# UC3843_Boost.net
KiCad netlist of a schematic drawn in Altium Designer
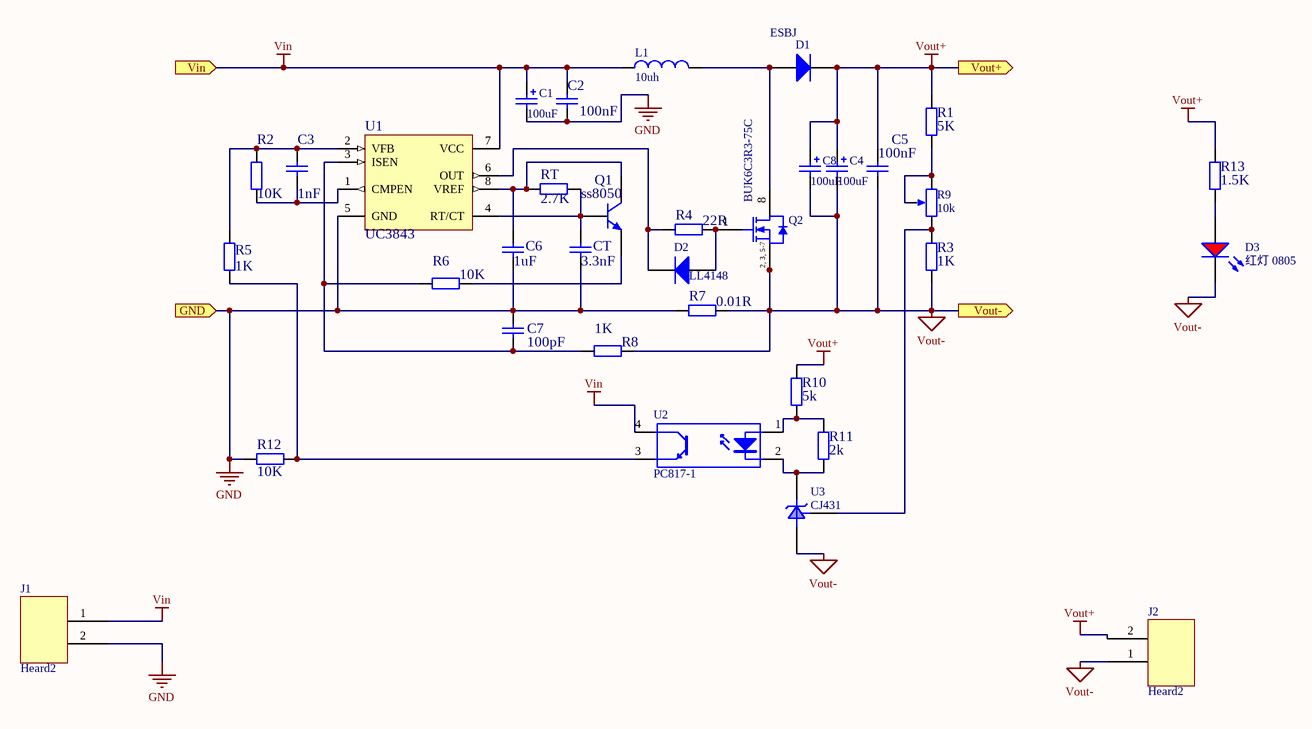
[diagram p0: UC3843_Boost.SchDoc]

(export (version "E")
  (design (tool "Eeschema 10.0.6"))
  (components
    (comp (ref "C1")
      (value "100uF")
      (footprint "CASE-B_3528")
      (description "钽电容")
      (libsource (lib "Miscellaneous Devices LC") (part "3528 100uF (107) 10% 6.3V"))
    )
    (comp (ref "C2")
      (value "100nF")
      (footprint "0805_C")
      (description "贴片电容")
      (libsource (lib "Miscellaneous Devices LC") (part "0805 100nF(104) 10% 50V"))
    )
    (comp (ref "C3")
      (value "1nF")
      (footprint "0805_C")
      (description "贴片电容")
      (libsource (lib "Miscellaneous Devices LC") (part "0805 100nF(104) 10% 50V"))
    )
    (comp (ref "C4")
      (value "100uF")
      (footprint "CASE-B_3528")
      (description "钽电容")
      (libsource (lib "Miscellaneous Devices LC") (part "3528 100uF (107) 10% 6.3V"))
    )
    (comp (ref "C5")
      (value "100nF")
      (footprint "0805_C")
      (description "贴片电容")
      (libsource (lib "Miscellaneous Devices LC") (part "0805 100nF(104) 10% 50V"))
    )
    (comp (ref "C6")
      (value "1uF")
      (footprint "0805R")
      (description "Capacitor")
      (fields (field (name "PUBLISHER") "Altium Limited"))
      (libsource (lib "Miscellaneous Devices") (part "Cap"))
    )
    (comp (ref "C7")
      (value "100pF")
      (footprint "0805R")
      (description "Capacitor")
      (fields (field (name "PUBLISHER") "Altium Limited"))
      (libsource (lib "Miscellaneous Devices") (part "Cap"))
    )
    (comp (ref "C8")
      (value "100uF")
      (footprint "CASE-B_3528")
      (description "钽电容")
      (libsource (lib "Miscellaneous Devices LC") (part "3528 100uF (107) 10% 6.3V"))
    )
    (comp (ref "CT")
      (value "3.3nF")
      (footprint "0805R")
      (description "Capacitor")
      (fields (field (name "PUBLISHER") "Altium Limited"))
      (libsource (lib "Miscellaneous Devices") (part "Cap"))
    )
    (comp (ref "D1")
      (value "ESBJ")
      (footprint "SMC(DO-214AB)_S1")
      (description "二极管")
      (libsource (lib "Miscellaneous Devices LC") (part "SMC(DO-214AB) SS36-E3/57T"))
    )
    (comp (ref "D2")
      (value "LL4148")
      (footprint "LL-34")
      (description "开关二极管")
      (libsource (lib "Miscellaneous Devices LC") (part "LL-34 LL4148 LL-34 1206"))
    )
    (comp (ref "D3")
      (value "红灯 0805")
      (footprint "0805_LED_S1")
      (description "发光二极管")
      (libsource (lib "Miscellaneous Devices LC") (part "0805 红灯"))
    )
    (comp (ref "J1") (value "Heard2") (footprint "8.5端子") (libsource (lib "") (part "Header2_1")))
    (comp (ref "J2")
      (value "Heard2")
      (footprint "8.5端子")
      (libsource (lib "myIntegrated_Library1") (part "Header2"))
    )
    (comp (ref "L1")
      (value "10uh")
      (footprint "L_10uh")
      (libsource (lib "myIntegrated_Library1") (part "L_10uh_15A"))
    )
    (comp (ref "Q1")
      (value "ss8050")
      (footprint "SOT-23(SOT-23-3)")
      (description "三极管")
      (libsource (lib "Miscellaneous Devices LC") (part "SOT-23 SS8050 Y1"))
    )
    (comp (ref "Q2")
      (value "BUK6C3R3-75C")
      (footprint "NXP-SOT427_N")
      (description "N-Channel TrenchMOS Intermediate Level FET, 75 V, 181 A, 7-Pin SOT427, Tape and Reel")
      (fields
        (field (name "MANUFACTURER") "NXP Semiconductors")
        (field (name "PARTNUMBER") "BUK6C3R3-75C,118")
      )
      (libsource (lib "NXP Semiconductors Automotive MOSFETs") (part "BUK6C3R3-75C,118"))
    )
    (comp (ref "R1")
      (value "5K")
      (footprint "0805R")
      (description "Resistor")
      (fields (field (name "PUBLISHER") "Altium Limited"))
      (libsource (lib "Miscellaneous Devices") (part "Res2"))
    )
    (comp (ref "R2")
      (value "10K")
      (footprint "0805R")
      (description "Resistor")
      (fields (field (name "PUBLISHER") "Altium Limited"))
      (libsource (lib "") (part "Res2_2"))
    )
    (comp (ref "R3")
      (value "1K")
      (footprint "0805R")
      (description "Resistor")
      (fields (field (name "PUBLISHER") "Altium Limited"))
      (libsource (lib "Miscellaneous Devices") (part "Res2"))
    )
    (comp (ref "R4")
      (value "22R")
      (footprint "0805R")
      (description "Resistor")
      (fields (field (name "PUBLISHER") "Altium Limited"))
      (libsource (lib "") (part "Res2_1"))
    )
    (comp (ref "R5")
      (value "1K")
      (footprint "0805R")
      (description "Resistor")
      (fields (field (name "PUBLISHER") "Altium Limited"))
      (libsource (lib "") (part "Res2_2"))
    )
    (comp (ref "R6")
      (value "10K")
      (footprint "0805R")
      (description "Resistor")
      (fields (field (name "PUBLISHER") "Altium Limited"))
      (libsource (lib "") (part "Res2_3"))
    )
    (comp (ref "R7")
      (value "0.01R")
      (footprint "水泥电阻")
      (description "Resistor")
      (fields (field (name "PUBLISHER") "Altium Limited"))
      (libsource (lib "") (part "Res2_3"))
    )
    (comp (ref "R8")
      (value "1K")
      (footprint "0805R")
      (description "Resistor")
      (fields (field (name "PUBLISHER") "Altium Limited"))
      (libsource (lib "") (part "Res2_3"))
    )
    (comp (ref "R9") (value "10k") (footprint "电位器") (libsource (lib "myIntegrated_Library1") (part "滑动变阻器")))
    (comp (ref "R10")
      (value "5k")
      (footprint "0805R")
      (description "Resistor")
      (fields (field (name "PUBLISHER") "Altium Limited"))
      (libsource (lib "Miscellaneous Devices") (part "Res2"))
    )
    (comp (ref "R11")
      (value "2k")
      (footprint "0805R")
      (description "Resistor")
      (fields (field (name "PUBLISHER") "Altium Limited"))
      (libsource (lib "Miscellaneous Devices") (part "Res2"))
    )
    (comp (ref "R12")
      (value "10K")
      (footprint "0805R")
      (description "Resistor")
      (fields (field (name "PUBLISHER") "Altium Limited"))
      (libsource (lib "") (part "Res2_1"))
    )
    (comp (ref "R13")
      (value "1.5K")
      (footprint "0805R")
      (description "Resistor")
      (fields (field (name "PUBLISHER") "Altium Limited"))
      (libsource (lib "Miscellaneous Devices") (part "Res2"))
    )
    (comp (ref "RT")
      (value "2.7K")
      (footprint "0805R")
      (description "Resistor")
      (fields (field (name "PUBLISHER") "Altium Limited"))
      (libsource (lib "") (part "Res2_1"))
    )
    (comp (ref "U1")
      (value "UC3843")
      (footprint "SOIC-8_150mil")
      (description "开关电源")
      (libsource (lib "Miscellaneous Devices LC") (part "UC3843BD1R2G_[C16414]"))
    )
    (comp (ref "U2")
      (value "PC817-1")
      (footprint "LC-SMD-4")
      (libsource (lib "myIntegrated_Library1") (part "TLP521"))
    )
    (comp (ref "U3")
      (value "CJ431")
      (footprint "SOT-23(SOT-23-3)")
      (description "电压基准")
      (libsource (lib "Miscellaneous Devices LC") (part "CJ431 0.5%431_[C3113]"))
    )
  )
  (nets
    (net (code "1") (name "GND") (class "Default")
      (node (ref "C1") (pin "2") (pinfunction "2_2") (pintype "passive"))
      (node (ref "C2") (pin "1") (pinfunction "1_1") (pintype "passive"))
      (node (ref "C6") (pin "2") (pinfunction "2_2") (pintype "passive"))
      (node (ref "C7") (pin "2") (pinfunction "2_2") (pintype "passive"))
      (node (ref "CT") (pin "2") (pinfunction "2_2") (pintype "passive"))
      (node (ref "J1") (pin "2") (pinfunction "2_2") (pintype "passive"))
      (node (ref "R12") (pin "1") (pinfunction "1_1") (pintype "passive"))
      (node (ref "R7") (pin "2") (pinfunction "2_2") (pintype "passive"))
      (node (ref "U1") (pin "5") (pinfunction "GND_5") (pintype "power_in"))
    )
    (net (code "2") (name "Net-(D1-A)") (class "Default")
      (node (ref "D1") (pin "1") (pinfunction "A_1") (pintype "passive"))
      (node (ref "L1") (pin "2") (pinfunction "2_2") (pintype "passive"))
      (node (ref "Q2") (pin "8") (pinfunction "D_8") (pintype "passive"))
    )
    (net (code "3") (name "Net-(D2-A)") (class "Default")
      (node (ref "D2") (pin "1") (pinfunction "A_1") (pintype "passive"))
      (node (ref "Q2") (pin "1") (pinfunction "G_1") (pintype "passive"))
      (node (ref "R4") (pin "2") (pinfunction "2_2") (pintype "passive"))
    )
    (net (code "4") (name "Net-(D2-K)") (class "Default")
      (node (ref "D2") (pin "2") (pinfunction "K_2") (pintype "passive"))
      (node (ref "R4") (pin "1") (pinfunction "1_1") (pintype "passive"))
      (node (ref "U1") (pin "6") (pinfunction "OUT_6") (pintype "output"))
    )
    (net (code "5") (name "Net-(D3-PadA)") (class "Default")
      (node (ref "D3") (pin "A") (pinfunction "A_A") (pintype "passive"))
      (node (ref "R13") (pin "1") (pinfunction "1_1") (pintype "passive"))
    )
    (net (code "6") (name "Net-(Q1-B)") (class "Default")
      (node (ref "CT") (pin "1") (pinfunction "1_1") (pintype "passive"))
      (node (ref "Q1") (pin "1") (pinfunction "B_1") (pintype "passive"))
      (node (ref "RT") (pin "2") (pinfunction "2_2") (pintype "passive"))
      (node (ref "U1") (pin "4") (pinfunction "RT/CT_4") (pintype "passive"))
    )
    (net (code "7") (name "Net-(Q1-C)") (class "Default")
      (node (ref "C6") (pin "1") (pinfunction "1_1") (pintype "passive"))
      (node (ref "Q1") (pin "3") (pinfunction "C_3") (pintype "passive"))
      (node (ref "RT") (pin "1") (pinfunction "1_1") (pintype "passive"))
      (node (ref "U1") (pin "8") (pinfunction "VREF_8") (pintype "output"))
    )
    (net (code "8") (name "Net-(Q1-E)") (class "Default")
      (node (ref "Q1") (pin "2") (pinfunction "E_2") (pintype "passive"))
      (node (ref "R6") (pin "1") (pinfunction "1_1") (pintype "passive"))
    )
    (net (code "9") (name "Net-(R1-Pad1)") (class "Default")
      (node (ref "R1") (pin "1") (pinfunction "1_1") (pintype "passive"))
      (node (ref "R9") (pin "2") (pinfunction "2_2") (pintype "passive"))
      (node (ref "R9") (pin "3") (pinfunction "3_3") (pintype "passive"))
    )
    (net (code "10") (name "Net-(U1-CMPEN)") (class "Default")
      (node (ref "C3") (pin "1") (pinfunction "1_1") (pintype "passive"))
      (node (ref "R2") (pin "2") (pinfunction "2_2") (pintype "passive"))
      (node (ref "U1") (pin "1") (pinfunction "CMPEN_1") (pintype "output"))
    )
    (net (code "11") (name "Net-(U1-ISEN)") (class "Default")
      (node (ref "C7") (pin "1") (pinfunction "1_1") (pintype "passive"))
      (node (ref "R6") (pin "2") (pinfunction "2_2") (pintype "passive"))
      (node (ref "R8") (pin "2") (pinfunction "2_2") (pintype "passive"))
      (node (ref "U1") (pin "3") (pinfunction "ISEN_3") (pintype "input"))
    )
    (net (code "12") (name "Net-(U1-VFB)") (class "Default")
      (node (ref "C3") (pin "2") (pinfunction "2_2") (pintype "passive"))
      (node (ref "R2") (pin "1") (pinfunction "1_1") (pintype "passive"))
      (node (ref "R5") (pin "1") (pinfunction "1_1") (pintype "passive"))
      (node (ref "U1") (pin "2") (pinfunction "VFB_2") (pintype "input"))
    )
    (net (code "13") (name "Net-(U2-A)") (class "Default")
      (node (ref "R10") (pin "1") (pinfunction "1_1") (pintype "passive"))
      (node (ref "R11") (pin "2") (pinfunction "2_2") (pintype "passive"))
      (node (ref "U2") (pin "1") (pinfunction "A_1") (pintype "passive"))
    )
    (net (code "14") (name "Net-(U2-E)") (class "Default")
      (node (ref "R12") (pin "2") (pinfunction "2_2") (pintype "passive"))
      (node (ref "R5") (pin "2") (pinfunction "2_2") (pintype "passive"))
      (node (ref "U2") (pin "3") (pinfunction "E_3") (pintype "passive"))
    )
    (net (code "15") (name "Net-(U2-K)") (class "Default")
      (node (ref "R11") (pin "1") (pinfunction "1_1") (pintype "passive"))
      (node (ref "U2") (pin "2") (pinfunction "K_2") (pintype "passive"))
      (node (ref "U3") (pin "2") (pinfunction "K_2") (pintype "passive"))
    )
    (net (code "16") (name "Net-(U3-R)") (class "Default")
      (node (ref "R3") (pin "2") (pinfunction "2_2") (pintype "passive"))
      (node (ref "R9") (pin "1") (pinfunction "1_1") (pintype "passive"))
      (node (ref "U3") (pin "1") (pinfunction "R_1") (pintype "passive"))
    )
    (net (code "17") (name "Vin") (class "Default")
      (node (ref "C1") (pin "1") (pinfunction "1_1") (pintype "passive"))
      (node (ref "C2") (pin "2") (pinfunction "2_2") (pintype "passive"))
      (node (ref "J1") (pin "1") (pinfunction "1_1") (pintype "passive"))
      (node (ref "L1") (pin "1") (pinfunction "1_1") (pintype "passive"))
      (node (ref "U1") (pin "7") (pinfunction "VCC_7") (pintype "power_in"))
      (node (ref "U2") (pin "4") (pinfunction "C_4") (pintype "passive"))
    )
    (net (code "18") (name "Vout+") (class "Default")
      (node (ref "C4") (pin "1") (pinfunction "1_1") (pintype "passive"))
      (node (ref "C5") (pin "2") (pinfunction "2_2") (pintype "passive"))
      (node (ref "C8") (pin "1") (pinfunction "1_1") (pintype "passive"))
      (node (ref "D1") (pin "2") (pinfunction "K_2") (pintype "passive"))
      (node (ref "J2") (pin "2") (pinfunction "2_2") (pintype "passive"))
      (node (ref "R1") (pin "2") (pinfunction "2_2") (pintype "passive"))
      (node (ref "R10") (pin "2") (pinfunction "2_2") (pintype "passive"))
      (node (ref "R13") (pin "2") (pinfunction "2_2") (pintype "passive"))
    )
    (net (code "19") (name "Vout-") (class "Default")
      (node (ref "C4") (pin "2") (pinfunction "2_2") (pintype "passive"))
      (node (ref "C5") (pin "1") (pinfunction "1_1") (pintype "passive"))
      (node (ref "C8") (pin "2") (pinfunction "2_2") (pintype "passive"))
      (node (ref "D3") (pin "K") (pinfunction "K_K") (pintype "passive"))
      (node (ref "J2") (pin "1") (pinfunction "1_1") (pintype "passive"))
      (node (ref "Q2") (pin "2") (pinfunction "S_2") (pintype "passive"))
      (node (ref "Q2") (pin "3") (pinfunction "S_3") (pintype "passive"))
      (node (ref "Q2") (pin "5") (pinfunction "S_5") (pintype "passive"))
      (node (ref "Q2") (pin "6") (pinfunction "S_6") (pintype "passive"))
      (node (ref "Q2") (pin "7") (pinfunction "S_7") (pintype "passive"))
      (node (ref "R3") (pin "1") (pinfunction "1_1") (pintype "passive"))
      (node (ref "R7") (pin "1") (pinfunction "1_1") (pintype "passive"))
      (node (ref "R8") (pin "1") (pinfunction "1_1") (pintype "passive"))
      (node (ref "U3") (pin "3") (pinfunction "A_3") (pintype "passive"))
    )
  )
)
